# digit.net
KiCad netlist of a schematic drawn in EAGLE
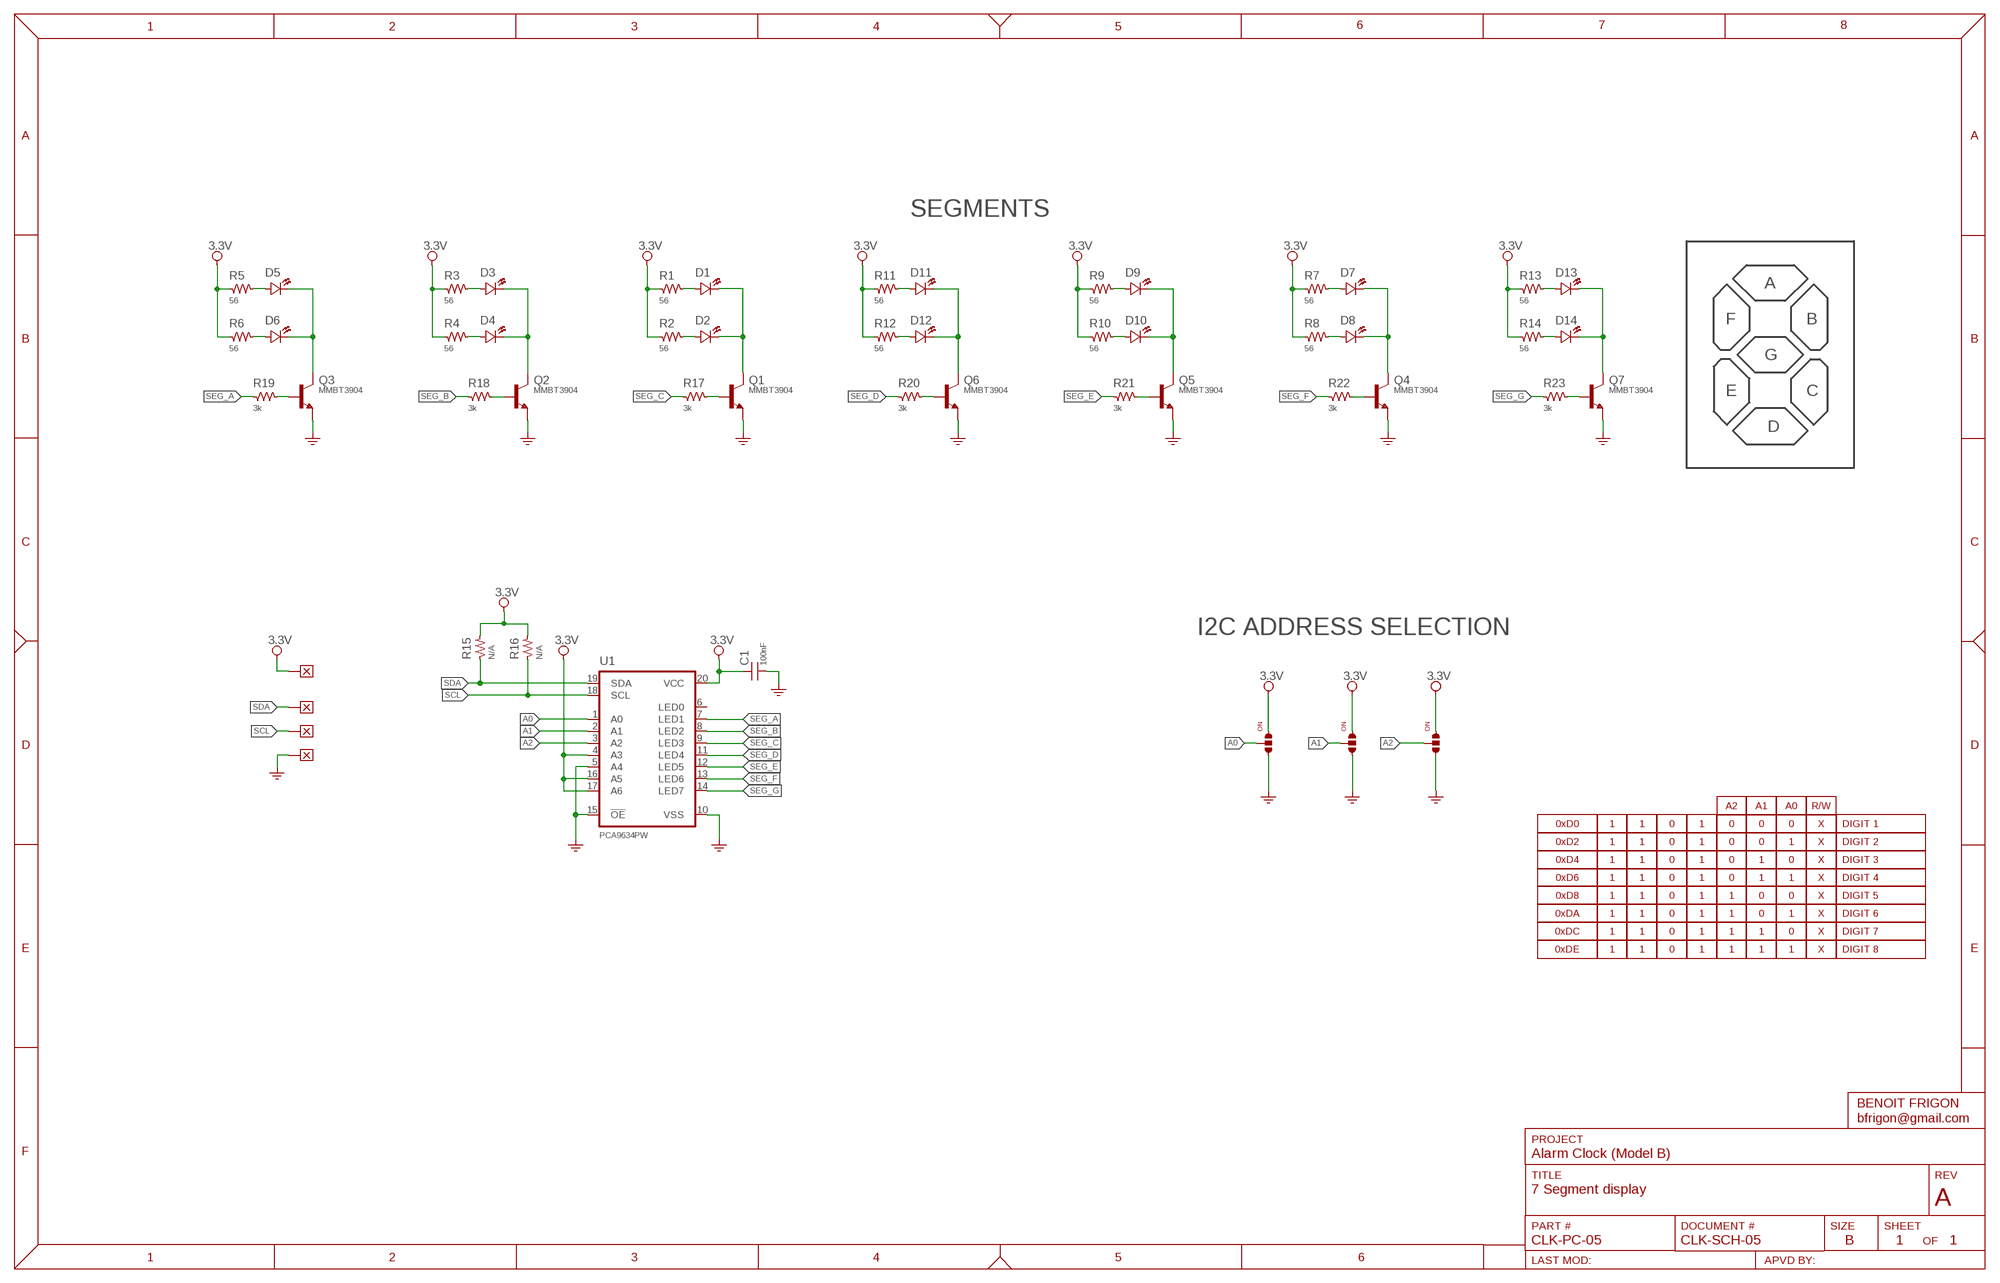
[diagram p0: schematic, sheet 1]

(export (version "E")
  (design (tool "Eeschema 10.0.6"))
  (components
    (comp (ref "C1")
      (value "100nF")
      (footprint "eagle-import:SMD_0603")
      (libsource (lib "eagle-import") (part "CAP-0603"))
    )
    (comp (ref "D1")
      (value "Red")
      (footprint "eagle-import:CHIPLED_0805")
      (fields
        (field (name "COLOR") "Red")
        (field (name "MFG") "Kingbright")
        (field (name "SKU") "APT2012SECK/J3-PRV")
      )
      (libsource (lib "eagle-import") (part "LED-0805"))
    )
    (comp (ref "D2")
      (value "Red")
      (footprint "eagle-import:CHIPLED_0805")
      (fields
        (field (name "COLOR") "Red")
        (field (name "MFG") "Kingbright")
        (field (name "SKU") "APT2012SECK/J3-PRV")
      )
      (libsource (lib "eagle-import") (part "LED-0805"))
    )
    (comp (ref "D3")
      (value "Red")
      (footprint "eagle-import:CHIPLED_0805")
      (fields
        (field (name "COLOR") "Red")
        (field (name "MFG") "Kingbright")
        (field (name "SKU") "APT2012SECK/J3-PRV")
      )
      (libsource (lib "eagle-import") (part "LED-0805"))
    )
    (comp (ref "D4")
      (value "Red")
      (footprint "eagle-import:CHIPLED_0805")
      (description "{DESCRIPTION} Chip 0805 - {ATTR:COLOR}")
      (fields
        (field (name "COLOR") "Red")
        (field (name "MFG") "Kingbright")
        (field (name "PACKAGE") "SMT 0805")
        (field (name "SKU") "APT2012SECK/J3-PRV")
      )
      (libsource (lib "eagle-import") (part "LED-0805"))
    )
    (comp (ref "D5")
      (value "Red")
      (footprint "eagle-import:CHIPLED_0805")
      (description "{DESCRIPTION} Chip 0805 - {ATTR:COLOR}")
      (fields
        (field (name "COLOR") "Red")
        (field (name "MFG") "Kingbright")
        (field (name "PACKAGE") "SMT 0805")
        (field (name "SKU") "APT2012SECK/J3-PRV")
      )
      (libsource (lib "eagle-import") (part "LED-0805"))
    )
    (comp (ref "D6")
      (value "Red")
      (footprint "eagle-import:CHIPLED_0805")
      (description "{DESCRIPTION} Chip 0805 - {ATTR:COLOR}")
      (fields
        (field (name "COLOR") "Red")
        (field (name "MFG") "Kingbright")
        (field (name "PACKAGE") "SMT 0805")
        (field (name "SKU") "APT2012SECK/J3-PRV")
      )
      (libsource (lib "eagle-import") (part "LED-0805"))
    )
    (comp (ref "D7")
      (value "Red")
      (footprint "eagle-import:CHIPLED_0805")
      (fields
        (field (name "COLOR") "Red")
        (field (name "MFG") "Kingbright")
        (field (name "SKU") "APT2012SECK/J3-PRV")
      )
      (libsource (lib "eagle-import") (part "LED-0805"))
    )
    (comp (ref "D8")
      (value "Red")
      (footprint "eagle-import:CHIPLED_0805")
      (fields
        (field (name "COLOR") "Red")
        (field (name "MFG") "Kingbright")
        (field (name "SKU") "APT2012SECK/J3-PRV")
      )
      (libsource (lib "eagle-import") (part "LED-0805"))
    )
    (comp (ref "D9")
      (value "Red")
      (footprint "eagle-import:CHIPLED_0805")
      (fields
        (field (name "COLOR") "Red")
        (field (name "MFG") "Kingbright")
        (field (name "SKU") "APT2012SECK/J3-PRV")
      )
      (libsource (lib "eagle-import") (part "LED-0805"))
    )
    (comp (ref "D10")
      (value "Red")
      (footprint "eagle-import:CHIPLED_0805")
      (fields
        (field (name "COLOR") "Red")
        (field (name "MFG") "Kingbright")
        (field (name "SKU") "APT2012SECK/J3-PRV")
      )
      (libsource (lib "eagle-import") (part "LED-0805"))
    )
    (comp (ref "D11")
      (value "Red")
      (footprint "eagle-import:CHIPLED_0805")
      (description "{DESCRIPTION} Chip 0805 - {ATTR:COLOR}")
      (fields
        (field (name "COLOR") "Red")
        (field (name "MFG") "Kingbright")
        (field (name "PACKAGE") "SMT 0805")
        (field (name "SKU") "APT2012SECK/J3-PRV")
      )
      (libsource (lib "eagle-import") (part "LED-0805"))
    )
    (comp (ref "D12")
      (value "Red")
      (footprint "eagle-import:CHIPLED_0805")
      (description "{DESCRIPTION} Chip 0805 - {ATTR:COLOR}")
      (fields
        (field (name "COLOR") "Red")
        (field (name "MFG") "Kingbright")
        (field (name "PACKAGE") "SMT 0805")
        (field (name "SKU") "APT2012SECK/J3-PRV")
      )
      (libsource (lib "eagle-import") (part "LED-0805"))
    )
    (comp (ref "D13")
      (value "Red")
      (footprint "eagle-import:CHIPLED_0805")
      (description "{DESCRIPTION} Chip 0805 - {ATTR:COLOR}")
      (fields
        (field (name "COLOR") "Red")
        (field (name "MFG") "Kingbright")
        (field (name "PACKAGE") "SMT 0805")
        (field (name "SKU") "APT2012SECK/J3-PRV")
      )
      (libsource (lib "eagle-import") (part "LED-0805"))
    )
    (comp (ref "D14")
      (value "Red")
      (footprint "eagle-import:CHIPLED_0805")
      (description "{DESCRIPTION} Chip 0805 - {ATTR:COLOR}")
      (fields
        (field (name "COLOR") "Red")
        (field (name "MFG") "Kingbright")
        (field (name "PACKAGE") "SMT 0805")
        (field (name "SKU") "APT2012SECK/J3-PRV")
      )
      (libsource (lib "eagle-import") (part "LED-0805"))
    )
    (comp (ref "J1")
      (value "SOLDER_JUMPER_3")
      (footprint "eagle-import:SOLDER_JUMPER_3")
      (libsource (lib "eagle-import") (part "SOLDER_JUMPER_3"))
    )
    (comp (ref "J2")
      (value "SOLDER_JUMPER_3")
      (footprint "eagle-import:SOLDER_JUMPER_3")
      (libsource (lib "eagle-import") (part "SOLDER_JUMPER_3"))
    )
    (comp (ref "J3")
      (value "SOLDER_JUMPER_3")
      (footprint "eagle-import:SOLDER_JUMPER_3")
      (libsource (lib "eagle-import") (part "SOLDER_JUMPER_3"))
    )
    (comp (ref "Q1")
      (value "MMBT3904")
      (footprint "eagle-import:SOT23")
      (libsource (lib "eagle-import") (part "MMBT3904"))
    )
    (comp (ref "Q2")
      (value "MMBT3904")
      (footprint "eagle-import:SOT23")
      (libsource (lib "eagle-import") (part "MMBT3904"))
    )
    (comp (ref "Q3")
      (value "MMBT3904")
      (footprint "eagle-import:SOT23")
      (libsource (lib "eagle-import") (part "MMBT3904"))
    )
    (comp (ref "Q4")
      (value "MMBT3904")
      (footprint "eagle-import:SOT23")
      (libsource (lib "eagle-import") (part "MMBT3904"))
    )
    (comp (ref "Q5")
      (value "MMBT3904")
      (footprint "eagle-import:SOT23")
      (libsource (lib "eagle-import") (part "MMBT3904"))
    )
    (comp (ref "Q6")
      (value "MMBT3904")
      (footprint "eagle-import:SOT23")
      (libsource (lib "eagle-import") (part "MMBT3904"))
    )
    (comp (ref "Q7")
      (value "MMBT3904")
      (footprint "eagle-import:SOT23")
      (libsource (lib "eagle-import") (part "MMBT3904"))
    )
    (comp (ref "R1")
      (value "56")
      (footprint "eagle-import:SMD_0603")
      (libsource (lib "eagle-import") (part "RES-0603"))
    )
    (comp (ref "R2")
      (value "56")
      (footprint "eagle-import:SMD_0603")
      (description "{DESCRIPTION} - SMT 0603 - {VALUE}")
      (fields (field (name "PACKAGE") "SMT 0603"))
      (libsource (lib "eagle-import") (part "RES-0603"))
    )
    (comp (ref "R3")
      (value "56")
      (footprint "eagle-import:SMD_0603")
      (description "{DESCRIPTION} - SMT 0603 - {VALUE}")
      (fields (field (name "PACKAGE") "SMT 0603"))
      (libsource (lib "eagle-import") (part "RES-0603"))
    )
    (comp (ref "R4")
      (value "56")
      (footprint "eagle-import:SMD_0603")
      (description "{DESCRIPTION} - SMT 0603 - {VALUE}")
      (fields (field (name "PACKAGE") "SMT 0603"))
      (libsource (lib "eagle-import") (part "RES-0603"))
    )
    (comp (ref "R5")
      (value "56")
      (footprint "eagle-import:SMD_0603")
      (description "{DESCRIPTION} - SMT 0603 - {VALUE}")
      (fields (field (name "PACKAGE") "SMT 0603"))
      (libsource (lib "eagle-import") (part "RES-0603"))
    )
    (comp (ref "R6")
      (value "56")
      (footprint "eagle-import:SMD_0603")
      (description "{DESCRIPTION} - SMT 0603 - {VALUE}")
      (fields (field (name "PACKAGE") "SMT 0603"))
      (libsource (lib "eagle-import") (part "RES-0603"))
    )
    (comp (ref "R7")
      (value "56")
      (footprint "eagle-import:SMD_0603")
      (description "{DESCRIPTION} - SMT 0603 - {VALUE}")
      (fields (field (name "PACKAGE") "SMT 0603"))
      (libsource (lib "eagle-import") (part "RES-0603"))
    )
    (comp (ref "R8")
      (value "56")
      (footprint "eagle-import:SMD_0603")
      (description "{DESCRIPTION} - SMT 0603 - {VALUE}")
      (fields (field (name "PACKAGE") "SMT 0603"))
      (libsource (lib "eagle-import") (part "RES-0603"))
    )
    (comp (ref "R9")
      (value "56")
      (footprint "eagle-import:SMD_0603")
      (description "{DESCRIPTION} - SMT 0603 - {VALUE}")
      (fields (field (name "PACKAGE") "SMT 0603"))
      (libsource (lib "eagle-import") (part "RES-0603"))
    )
    (comp (ref "R10")
      (value "56")
      (footprint "eagle-import:SMD_0603")
      (description "{DESCRIPTION} - SMT 0603 - {VALUE}")
      (fields (field (name "PACKAGE") "SMT 0603"))
      (libsource (lib "eagle-import") (part "RES-0603"))
    )
    (comp (ref "R11")
      (value "56")
      (footprint "eagle-import:SMD_0603")
      (description "{DESCRIPTION} - SMT 0603 - {VALUE}")
      (fields (field (name "PACKAGE") "SMT 0603"))
      (libsource (lib "eagle-import") (part "RES-0603"))
    )
    (comp (ref "R12")
      (value "56")
      (footprint "eagle-import:SMD_0603")
      (description "{DESCRIPTION} - SMT 0603 - {VALUE}")
      (fields (field (name "PACKAGE") "SMT 0603"))
      (libsource (lib "eagle-import") (part "RES-0603"))
    )
    (comp (ref "R13")
      (value "56")
      (footprint "eagle-import:SMD_0603")
      (description "{DESCRIPTION} - SMT 0603 - {VALUE}")
      (fields (field (name "PACKAGE") "SMT 0603"))
      (libsource (lib "eagle-import") (part "RES-0603"))
    )
    (comp (ref "R14")
      (value "56")
      (footprint "eagle-import:SMD_0603")
      (description "{DESCRIPTION} - SMT 0603 - {VALUE}")
      (fields (field (name "PACKAGE") "SMT 0603"))
      (libsource (lib "eagle-import") (part "RES-0603"))
    )
    (comp (ref "R15")
      (value "N/A")
      (footprint "eagle-import:SMD_0603")
      (libsource (lib "eagle-import") (part "RES-0603"))
    )
    (comp (ref "R16")
      (value "N/A")
      (footprint "eagle-import:SMD_0603")
      (libsource (lib "eagle-import") (part "RES-0603"))
    )
    (comp (ref "R17")
      (value "3k")
      (footprint "eagle-import:SMD_0603")
      (libsource (lib "eagle-import") (part "RES-0603"))
    )
    (comp (ref "R18")
      (value "3k")
      (footprint "eagle-import:SMD_0603")
      (description "{DESCRIPTION} - SMT 0603 - {VALUE}")
      (fields (field (name "PACKAGE") "SMT 0603"))
      (libsource (lib "eagle-import") (part "RES-0603"))
    )
    (comp (ref "R19")
      (value "3k")
      (footprint "eagle-import:SMD_0603")
      (description "{DESCRIPTION} - SMT 0603 - {VALUE}")
      (fields (field (name "PACKAGE") "SMT 0603"))
      (libsource (lib "eagle-import") (part "RES-0603"))
    )
    (comp (ref "R20")
      (value "3k")
      (footprint "eagle-import:SMD_0603")
      (description "{DESCRIPTION} - SMT 0603 - {VALUE}")
      (fields (field (name "PACKAGE") "SMT 0603"))
      (libsource (lib "eagle-import") (part "RES-0603"))
    )
    (comp (ref "R21")
      (value "3k")
      (footprint "eagle-import:SMD_0603")
      (description "{DESCRIPTION} - SMT 0603 - {VALUE}")
      (fields (field (name "PACKAGE") "SMT 0603"))
      (libsource (lib "eagle-import") (part "RES-0603"))
    )
    (comp (ref "R22")
      (value "3k")
      (footprint "eagle-import:SMD_0603")
      (description "{DESCRIPTION} - SMT 0603 - {VALUE}")
      (fields (field (name "PACKAGE") "SMT 0603"))
      (libsource (lib "eagle-import") (part "RES-0603"))
    )
    (comp (ref "R23")
      (value "3k")
      (footprint "eagle-import:SMD_0603")
      (description "{DESCRIPTION} - SMT 0603 - {VALUE}")
      (fields (field (name "PACKAGE") "SMT 0603"))
      (libsource (lib "eagle-import") (part "RES-0603"))
    )
    (comp (ref "U1")
      (value "PCA9634PW")
      (footprint "eagle-import:TSSOP20")
      (fields (field (name "MFG") "NXP Semiconductors"))
      (libsource (lib "eagle-import") (part "PCA9634PW"))
    )
    (comp (ref "W1")
      (value "WIRE")
      (footprint "eagle-import:WIRE_SMT")
      (libsource (lib "eagle-import") (part "WIRE"))
    )
    (comp (ref "W2")
      (value "WIRE")
      (footprint "eagle-import:WIRE_SMT")
      (libsource (lib "eagle-import") (part "WIRE"))
    )
    (comp (ref "W3")
      (value "WIRE")
      (footprint "eagle-import:WIRE_SMT")
      (libsource (lib "eagle-import") (part "WIRE"))
    )
    (comp (ref "W4")
      (value "WIRE")
      (footprint "eagle-import:WIRE_SMT")
      (libsource (lib "eagle-import") (part "WIRE"))
    )
  )
  (nets
    (net (code "1") (name "3.3V") (class "Default")
      (node (ref "C1") (pin "1") (pinfunction "1_1") (pintype "passive"))
      (node (ref "J1") (pin "1") (pinfunction "1_1") (pintype "bidirectional"))
      (node (ref "J2") (pin "1") (pinfunction "1_1") (pintype "bidirectional"))
      (node (ref "J3") (pin "1") (pinfunction "1_1") (pintype "bidirectional"))
      (node (ref "R1") (pin "1") (pinfunction "1_1") (pintype "passive"))
      (node (ref "R10") (pin "1") (pinfunction "1_1") (pintype "passive"))
      (node (ref "R11") (pin "1") (pinfunction "1_1") (pintype "passive"))
      (node (ref "R12") (pin "1") (pinfunction "1_1") (pintype "passive"))
      (node (ref "R13") (pin "1") (pinfunction "1_1") (pintype "passive"))
      (node (ref "R14") (pin "1") (pinfunction "1_1") (pintype "passive"))
      (node (ref "R15") (pin "2") (pinfunction "2_2") (pintype "passive"))
      (node (ref "R16") (pin "2") (pinfunction "2_2") (pintype "passive"))
      (node (ref "R2") (pin "1") (pinfunction "1_1") (pintype "passive"))
      (node (ref "R3") (pin "1") (pinfunction "1_1") (pintype "passive"))
      (node (ref "R4") (pin "1") (pinfunction "1_1") (pintype "passive"))
      (node (ref "R5") (pin "1") (pinfunction "1_1") (pintype "passive"))
      (node (ref "R6") (pin "1") (pinfunction "1_1") (pintype "passive"))
      (node (ref "R7") (pin "1") (pinfunction "1_1") (pintype "passive"))
      (node (ref "R8") (pin "1") (pinfunction "1_1") (pintype "passive"))
      (node (ref "R9") (pin "1") (pinfunction "1_1") (pintype "passive"))
      (node (ref "U1") (pin "16") (pinfunction "A5_16") (pintype "bidirectional"))
      (node (ref "U1") (pin "17") (pinfunction "A6_17") (pintype "bidirectional"))
      (node (ref "U1") (pin "20") (pinfunction "VCC_20") (pintype "bidirectional"))
      (node (ref "U1") (pin "4") (pinfunction "A3_4") (pintype "bidirectional"))
      (node (ref "W1") (pin "1") (pinfunction "P$1_1") (pintype "bidirectional"))
    )
    (net (code "2") (name "A0") (class "Default")
      (node (ref "J2") (pin "2") (pinfunction "2_2") (pintype "bidirectional"))
      (node (ref "U1") (pin "1") (pinfunction "A0_1") (pintype "bidirectional"))
    )
    (net (code "3") (name "A1") (class "Default")
      (node (ref "J1") (pin "2") (pinfunction "2_2") (pintype "bidirectional"))
      (node (ref "U1") (pin "2") (pinfunction "A1_2") (pintype "bidirectional"))
    )
    (net (code "4") (name "A2") (class "Default")
      (node (ref "J3") (pin "2") (pinfunction "2_2") (pintype "bidirectional"))
      (node (ref "U1") (pin "3") (pinfunction "A2_3") (pintype "bidirectional"))
    )
    (net (code "5") (name "GND") (class "Default")
      (node (ref "C1") (pin "2") (pinfunction "2_2") (pintype "passive"))
      (node (ref "J1") (pin "3") (pinfunction "3_3") (pintype "bidirectional"))
      (node (ref "J2") (pin "3") (pinfunction "3_3") (pintype "bidirectional"))
      (node (ref "J3") (pin "3") (pinfunction "3_3") (pintype "bidirectional"))
      (node (ref "Q1") (pin "2") (pinfunction "E_2") (pintype "passive"))
      (node (ref "Q2") (pin "2") (pinfunction "E_2") (pintype "passive"))
      (node (ref "Q3") (pin "2") (pinfunction "E_2") (pintype "passive"))
      (node (ref "Q4") (pin "2") (pinfunction "E_2") (pintype "passive"))
      (node (ref "Q5") (pin "2") (pinfunction "E_2") (pintype "passive"))
      (node (ref "Q6") (pin "2") (pinfunction "E_2") (pintype "passive"))
      (node (ref "Q7") (pin "2") (pinfunction "E_2") (pintype "passive"))
      (node (ref "U1") (pin "10") (pinfunction "VSS_10") (pintype "bidirectional"))
      (node (ref "U1") (pin "15") (pinfunction "~{OE}_15") (pintype "bidirectional"))
      (node (ref "U1") (pin "5") (pinfunction "A4_5") (pintype "bidirectional"))
      (node (ref "W4") (pin "1") (pinfunction "P$1_1") (pintype "bidirectional"))
    )
    (net (code "6") (name "Net-(D1-PadA)") (class "Default")
      (node (ref "D1") (pin "A") (pinfunction "A_A") (pintype "passive"))
      (node (ref "R1") (pin "2") (pinfunction "2_2") (pintype "passive"))
    )
    (net (code "7") (name "Net-(D2-PadA)") (class "Default")
      (node (ref "D2") (pin "A") (pinfunction "A_A") (pintype "passive"))
      (node (ref "R2") (pin "2") (pinfunction "2_2") (pintype "passive"))
    )
    (net (code "8") (name "Net-(D3-PadA)") (class "Default")
      (node (ref "D3") (pin "A") (pinfunction "A_A") (pintype "passive"))
      (node (ref "R3") (pin "2") (pinfunction "2_2") (pintype "passive"))
    )
    (net (code "9") (name "Net-(D4-PadA)") (class "Default")
      (node (ref "D4") (pin "A") (pinfunction "A_A") (pintype "passive"))
      (node (ref "R4") (pin "2") (pinfunction "2_2") (pintype "passive"))
    )
    (net (code "10") (name "Net-(D5-PadA)") (class "Default")
      (node (ref "D5") (pin "A") (pinfunction "A_A") (pintype "passive"))
      (node (ref "R5") (pin "2") (pinfunction "2_2") (pintype "passive"))
    )
    (net (code "11") (name "Net-(D6-PadA)") (class "Default")
      (node (ref "D6") (pin "A") (pinfunction "A_A") (pintype "passive"))
      (node (ref "R6") (pin "2") (pinfunction "2_2") (pintype "passive"))
    )
    (net (code "12") (name "Net-(D7-PadA)") (class "Default")
      (node (ref "D7") (pin "A") (pinfunction "A_A") (pintype "passive"))
      (node (ref "R7") (pin "2") (pinfunction "2_2") (pintype "passive"))
    )
    (net (code "13") (name "Net-(D8-PadA)") (class "Default")
      (node (ref "D8") (pin "A") (pinfunction "A_A") (pintype "passive"))
      (node (ref "R8") (pin "2") (pinfunction "2_2") (pintype "passive"))
    )
    (net (code "14") (name "Net-(D9-PadA)") (class "Default")
      (node (ref "D9") (pin "A") (pinfunction "A_A") (pintype "passive"))
      (node (ref "R9") (pin "2") (pinfunction "2_2") (pintype "passive"))
    )
    (net (code "15") (name "Net-(D10-PadA)") (class "Default")
      (node (ref "D10") (pin "A") (pinfunction "A_A") (pintype "passive"))
      (node (ref "R10") (pin "2") (pinfunction "2_2") (pintype "passive"))
    )
    (net (code "16") (name "Net-(D11-PadA)") (class "Default")
      (node (ref "D11") (pin "A") (pinfunction "A_A") (pintype "passive"))
      (node (ref "R11") (pin "2") (pinfunction "2_2") (pintype "passive"))
    )
    (net (code "17") (name "Net-(D12-PadA)") (class "Default")
      (node (ref "D12") (pin "A") (pinfunction "A_A") (pintype "passive"))
      (node (ref "R12") (pin "2") (pinfunction "2_2") (pintype "passive"))
    )
    (net (code "18") (name "Net-(D13-PadA)") (class "Default")
      (node (ref "D13") (pin "A") (pinfunction "A_A") (pintype "passive"))
      (node (ref "R13") (pin "2") (pinfunction "2_2") (pintype "passive"))
    )
    (net (code "19") (name "Net-(D14-PadA)") (class "Default")
      (node (ref "D14") (pin "A") (pinfunction "A_A") (pintype "passive"))
      (node (ref "R14") (pin "2") (pinfunction "2_2") (pintype "passive"))
    )
    (net (code "20") (name "Net-(Q1-B)") (class "Default")
      (node (ref "Q1") (pin "1") (pinfunction "B_1") (pintype "passive"))
      (node (ref "R17") (pin "2") (pinfunction "2_2") (pintype "passive"))
    )
    (net (code "21") (name "Net-(Q1-C)") (class "Default")
      (node (ref "D1") (pin "K") (pinfunction "K_K") (pintype "passive"))
      (node (ref "D2") (pin "K") (pinfunction "K_K") (pintype "passive"))
      (node (ref "Q1") (pin "3") (pinfunction "C_3") (pintype "passive"))
    )
    (net (code "22") (name "Net-(Q2-B)") (class "Default")
      (node (ref "Q2") (pin "1") (pinfunction "B_1") (pintype "passive"))
      (node (ref "R18") (pin "2") (pinfunction "2_2") (pintype "passive"))
    )
    (net (code "23") (name "Net-(Q2-C)") (class "Default")
      (node (ref "D3") (pin "K") (pinfunction "K_K") (pintype "passive"))
      (node (ref "D4") (pin "K") (pinfunction "K_K") (pintype "passive"))
      (node (ref "Q2") (pin "3") (pinfunction "C_3") (pintype "passive"))
    )
    (net (code "24") (name "Net-(Q3-B)") (class "Default")
      (node (ref "Q3") (pin "1") (pinfunction "B_1") (pintype "passive"))
      (node (ref "R19") (pin "2") (pinfunction "2_2") (pintype "passive"))
    )
    (net (code "25") (name "Net-(Q3-C)") (class "Default")
      (node (ref "D5") (pin "K") (pinfunction "K_K") (pintype "passive"))
      (node (ref "D6") (pin "K") (pinfunction "K_K") (pintype "passive"))
      (node (ref "Q3") (pin "3") (pinfunction "C_3") (pintype "passive"))
    )
    (net (code "26") (name "Net-(Q4-B)") (class "Default")
      (node (ref "Q4") (pin "1") (pinfunction "B_1") (pintype "passive"))
      (node (ref "R22") (pin "2") (pinfunction "2_2") (pintype "passive"))
    )
    (net (code "27") (name "Net-(Q4-C)") (class "Default")
      (node (ref "D7") (pin "K") (pinfunction "K_K") (pintype "passive"))
      (node (ref "D8") (pin "K") (pinfunction "K_K") (pintype "passive"))
      (node (ref "Q4") (pin "3") (pinfunction "C_3") (pintype "passive"))
    )
    (net (code "28") (name "Net-(Q5-B)") (class "Default")
      (node (ref "Q5") (pin "1") (pinfunction "B_1") (pintype "passive"))
      (node (ref "R21") (pin "2") (pinfunction "2_2") (pintype "passive"))
    )
    (net (code "29") (name "Net-(Q5-C)") (class "Default")
      (node (ref "D10") (pin "K") (pinfunction "K_K") (pintype "passive"))
      (node (ref "D9") (pin "K") (pinfunction "K_K") (pintype "passive"))
      (node (ref "Q5") (pin "3") (pinfunction "C_3") (pintype "passive"))
    )
    (net (code "30") (name "Net-(Q6-B)") (class "Default")
      (node (ref "Q6") (pin "1") (pinfunction "B_1") (pintype "passive"))
      (node (ref "R20") (pin "2") (pinfunction "2_2") (pintype "passive"))
    )
    (net (code "31") (name "Net-(Q6-C)") (class "Default")
      (node (ref "D11") (pin "K") (pinfunction "K_K") (pintype "passive"))
      (node (ref "D12") (pin "K") (pinfunction "K_K") (pintype "passive"))
      (node (ref "Q6") (pin "3") (pinfunction "C_3") (pintype "passive"))
    )
    (net (code "32") (name "Net-(Q7-B)") (class "Default")
      (node (ref "Q7") (pin "1") (pinfunction "B_1") (pintype "passive"))
      (node (ref "R23") (pin "2") (pinfunction "2_2") (pintype "passive"))
    )
    (net (code "33") (name "Net-(Q7-C)") (class "Default")
      (node (ref "D13") (pin "K") (pinfunction "K_K") (pintype "passive"))
      (node (ref "D14") (pin "K") (pinfunction "K_K") (pintype "passive"))
      (node (ref "Q7") (pin "3") (pinfunction "C_3") (pintype "passive"))
    )
    (net (code "34") (name "SCL") (class "Default")
      (node (ref "R16") (pin "1") (pinfunction "1_1") (pintype "passive"))
      (node (ref "U1") (pin "18") (pinfunction "SCL_18") (pintype "bidirectional"))
      (node (ref "W3") (pin "1") (pinfunction "P$1_1") (pintype "bidirectional"))
    )
    (net (code "35") (name "SDA") (class "Default")
      (node (ref "R15") (pin "1") (pinfunction "1_1") (pintype "passive"))
      (node (ref "U1") (pin "19") (pinfunction "SDA_19") (pintype "bidirectional"))
      (node (ref "W2") (pin "1") (pinfunction "P$1_1") (pintype "bidirectional"))
    )
    (net (code "36") (name "SEG_A") (class "Default")
      (node (ref "R19") (pin "1") (pinfunction "1_1") (pintype "passive"))
      (node (ref "U1") (pin "7") (pinfunction "LED1_7") (pintype "bidirectional"))
    )
    (net (code "37") (name "SEG_B") (class "Default")
      (node (ref "R18") (pin "1") (pinfunction "1_1") (pintype "passive"))
      (node (ref "U1") (pin "8") (pinfunction "LED2_8") (pintype "bidirectional"))
    )
    (net (code "38") (name "SEG_C") (class "Default")
      (node (ref "R17") (pin "1") (pinfunction "1_1") (pintype "passive"))
      (node (ref "U1") (pin "9") (pinfunction "LED3_9") (pintype "bidirectional"))
    )
    (net (code "39") (name "SEG_D") (class "Default")
      (node (ref "R20") (pin "1") (pinfunction "1_1") (pintype "passive"))
      (node (ref "U1") (pin "11") (pinfunction "LED4_11") (pintype "bidirectional"))
    )
    (net (code "40") (name "SEG_E") (class "Default")
      (node (ref "R21") (pin "1") (pinfunction "1_1") (pintype "passive"))
      (node (ref "U1") (pin "12") (pinfunction "LED5_12") (pintype "bidirectional"))
    )
    (net (code "41") (name "SEG_F") (class "Default")
      (node (ref "R22") (pin "1") (pinfunction "1_1") (pintype "passive"))
      (node (ref "U1") (pin "13") (pinfunction "LED6_13") (pintype "bidirectional"))
    )
    (net (code "42") (name "SEG_G") (class "Default")
      (node (ref "R23") (pin "1") (pinfunction "1_1") (pintype "passive"))
      (node (ref "U1") (pin "14") (pinfunction "LED7_14") (pintype "bidirectional"))
    )
    (net (code "43") (name "unconnected-(U1-LED0-Pad6)") (class "Default")
      (node (ref "U1") (pin "6") (pinfunction "LED0_6") (pintype "bidirectional"))
    )
  )
)
